# esp32-esp32s3_adapter.net
KiCad netlist of a schematic drawn in EAGLE
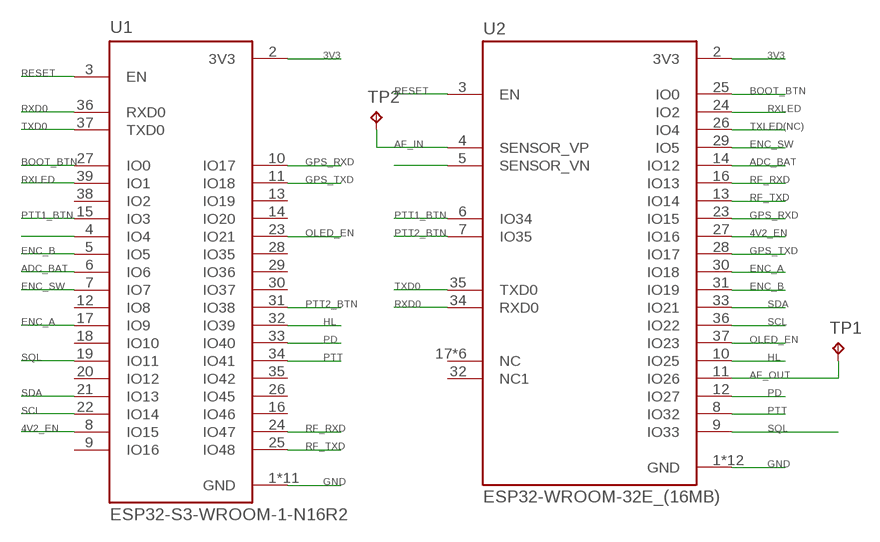
[diagram p0: schematic, sheet 1]

(export (version "E")
  (design (tool "Eeschema 10.0.6"))
  (components
    (comp (ref "TP1")
      (value "TPB1,27")
      (footprint "eagle-import:B1,27")
      (libsource (lib "eagle-import") (part "TPB1,27"))
    )
    (comp (ref "TP2")
      (value "TPB1,27")
      (footprint "eagle-import:B1,27")
      (libsource (lib "eagle-import") (part "TPB1,27"))
    )
    (comp (ref "U1")
      (value "ESP32-S3-WROOM-1-N16R2")
      (footprint "eagle-import:XCVR_ESP32-S3-WROOM-1-N16R2")
      (fields (field (name "MF") "Espressif Systems"))
      (libsource (lib "eagle-import") (part "ESP32-S3-WROOM-1-N16R2"))
    )
    (comp (ref "U2")
      (value "ESP32-WROOM-32E_(16MB)")
      (footprint "eagle-import:XCVR_ESP32-WROOM-32E_(16MB)")
      (fields (field (name "MF") "Espressif Systems") (field (name "MP") "ESP32-WROOM-32E (16MB)"))
      (libsource (lib "eagle-import") (part "ESP32-WROOM-32E_(16MB)"))
    )
  )
  (nets
    (net (code "1") (name "/3V3") (class "Default")
      (node (ref "U1") (pin "2") (pinfunction "3V3_2") (pintype "power_in"))
      (node (ref "U2") (pin "2") (pinfunction "3V3_2") (pintype "power_in"))
    )
    (net (code "2") (name "/4V2_EN") (class "Default")
      (node (ref "U1") (pin "8") (pinfunction "IO15_8") (pintype "bidirectional"))
      (node (ref "U2") (pin "27") (pinfunction "IO16_27") (pintype "bidirectional"))
    )
    (net (code "3") (name "/ADC_BAT") (class "Default")
      (node (ref "U1") (pin "6") (pinfunction "IO6_6") (pintype "bidirectional"))
      (node (ref "U2") (pin "14") (pinfunction "IO12_14") (pintype "bidirectional"))
    )
    (net (code "4") (name "/AF_IN") (class "Default")
      (node (ref "TP2") (pin "TP") (pinfunction "TP_TP") (pintype "input"))
      (node (ref "U2") (pin "4") (pinfunction "SENSOR_VP_4") (pintype "input"))
    )
    (net (code "5") (name "/AF_OUT") (class "Default")
      (node (ref "TP1") (pin "TP") (pinfunction "TP_TP") (pintype "input"))
      (node (ref "U2") (pin "11") (pinfunction "IO26_11") (pintype "bidirectional"))
    )
    (net (code "6") (name "/BOOT_BTN") (class "Default")
      (node (ref "U1") (pin "27") (pinfunction "IO0_27") (pintype "bidirectional"))
      (node (ref "U2") (pin "25") (pinfunction "IO0_25") (pintype "bidirectional"))
    )
    (net (code "7") (name "/ENC_A") (class "Default")
      (node (ref "U1") (pin "17") (pinfunction "IO9_17") (pintype "bidirectional"))
      (node (ref "U2") (pin "30") (pinfunction "IO18_30") (pintype "bidirectional"))
    )
    (net (code "8") (name "/ENC_B") (class "Default")
      (node (ref "U1") (pin "5") (pinfunction "IO5_5") (pintype "bidirectional"))
      (node (ref "U2") (pin "31") (pinfunction "IO19_31") (pintype "bidirectional"))
    )
    (net (code "9") (name "/ENC_SW") (class "Default")
      (node (ref "U1") (pin "7") (pinfunction "IO7_7") (pintype "bidirectional"))
      (node (ref "U2") (pin "29") (pinfunction "IO5_29") (pintype "bidirectional"))
    )
    (net (code "10") (name "/GND") (class "Default")
      (node (ref "U1") (pin "1") (pinfunction "GND_1") (pintype "power_in"))
      (node (ref "U1") (pin "40") (pinfunction "GND_40") (pintype "power_in"))
      (node (ref "U1") (pin "41_1") (pinfunction "GND_41_1") (pintype "power_in"))
      (node (ref "U1") (pin "41_2") (pinfunction "GND_41_2") (pintype "power_in"))
      (node (ref "U1") (pin "41_3") (pinfunction "GND_41_3") (pintype "power_in"))
      (node (ref "U1") (pin "41_4") (pinfunction "GND_41_4") (pintype "power_in"))
      (node (ref "U1") (pin "41_5") (pinfunction "GND_41_5") (pintype "power_in"))
      (node (ref "U1") (pin "41_6") (pinfunction "GND_41_6") (pintype "power_in"))
      (node (ref "U1") (pin "41_7") (pinfunction "GND_41_7") (pintype "power_in"))
      (node (ref "U1") (pin "41_8") (pinfunction "GND_41_8") (pintype "power_in"))
      (node (ref "U1") (pin "41_9") (pinfunction "GND_41_9") (pintype "power_in"))
      (node (ref "U2") (pin "1") (pinfunction "GND_1") (pintype "power_in"))
      (node (ref "U2") (pin "15") (pinfunction "GND_15") (pintype "power_in"))
      (node (ref "U2") (pin "38") (pinfunction "GND_38") (pintype "power_in"))
      (node (ref "U2") (pin "39_1") (pinfunction "GND_39_1") (pintype "power_in"))
      (node (ref "U2") (pin "39_2") (pinfunction "GND_39_2") (pintype "power_in"))
      (node (ref "U2") (pin "39_3") (pinfunction "GND_39_3") (pintype "power_in"))
      (node (ref "U2") (pin "39_4") (pinfunction "GND_39_4") (pintype "power_in"))
      (node (ref "U2") (pin "39_5") (pinfunction "GND_39_5") (pintype "power_in"))
      (node (ref "U2") (pin "39_6") (pinfunction "GND_39_6") (pintype "power_in"))
      (node (ref "U2") (pin "39_7") (pinfunction "GND_39_7") (pintype "power_in"))
      (node (ref "U2") (pin "39_8") (pinfunction "GND_39_8") (pintype "power_in"))
      (node (ref "U2") (pin "39_9") (pinfunction "GND_39_9") (pintype "power_in"))
    )
    (net (code "11") (name "/GPS_RXD") (class "Default")
      (node (ref "U1") (pin "10") (pinfunction "IO17_10") (pintype "bidirectional"))
      (node (ref "U2") (pin "23") (pinfunction "IO15_23") (pintype "bidirectional"))
    )
    (net (code "12") (name "/GPS_TXD") (class "Default")
      (node (ref "U1") (pin "11") (pinfunction "IO18_11") (pintype "bidirectional"))
      (node (ref "U2") (pin "28") (pinfunction "IO17_28") (pintype "bidirectional"))
    )
    (net (code "13") (name "/HL") (class "Default")
      (node (ref "U1") (pin "32") (pinfunction "IO39_32") (pintype "bidirectional"))
      (node (ref "U2") (pin "10") (pinfunction "IO25_10") (pintype "bidirectional"))
    )
    (net (code "14") (name "/OLED_EN") (class "Default")
      (node (ref "U1") (pin "23") (pinfunction "IO21_23") (pintype "bidirectional"))
      (node (ref "U2") (pin "37") (pinfunction "IO23_37") (pintype "bidirectional"))
    )
    (net (code "15") (name "/PD") (class "Default")
      (node (ref "U1") (pin "33") (pinfunction "IO40_33") (pintype "bidirectional"))
      (node (ref "U2") (pin "12") (pinfunction "IO27_12") (pintype "bidirectional"))
    )
    (net (code "16") (name "/PTT") (class "Default")
      (node (ref "U1") (pin "34") (pinfunction "IO41_34") (pintype "bidirectional"))
      (node (ref "U2") (pin "8") (pinfunction "IO32_8") (pintype "bidirectional"))
    )
    (net (code "17") (name "/PTT1_BTN") (class "Default")
      (node (ref "U1") (pin "15") (pinfunction "IO3_15") (pintype "bidirectional"))
      (node (ref "U2") (pin "6") (pinfunction "IO34_6") (pintype "input"))
    )
    (net (code "18") (name "/PTT2_BTN") (class "Default")
      (node (ref "U1") (pin "31") (pinfunction "IO38_31") (pintype "bidirectional"))
      (node (ref "U2") (pin "7") (pinfunction "IO35_7") (pintype "input"))
    )
    (net (code "19") (name "/RESET") (class "Default")
      (node (ref "U1") (pin "3") (pinfunction "EN_3") (pintype "input"))
      (node (ref "U2") (pin "3") (pinfunction "EN_3") (pintype "input"))
    )
    (net (code "20") (name "/RF_RXD") (class "Default")
      (node (ref "U1") (pin "24") (pinfunction "IO47_24") (pintype "bidirectional"))
      (node (ref "U2") (pin "16") (pinfunction "IO13_16") (pintype "bidirectional"))
    )
    (net (code "21") (name "/RF_TXD") (class "Default")
      (node (ref "U1") (pin "25") (pinfunction "IO48_25") (pintype "bidirectional"))
      (node (ref "U2") (pin "13") (pinfunction "IO14_13") (pintype "bidirectional"))
    )
    (net (code "22") (name "/RXD0") (class "Default")
      (node (ref "U1") (pin "36") (pinfunction "RXD0_36") (pintype "bidirectional"))
      (node (ref "U2") (pin "34") (pinfunction "RXD0_34") (pintype "bidirectional"))
    )
    (net (code "23") (name "/RXLED") (class "Default")
      (node (ref "U1") (pin "39") (pinfunction "IO1_39") (pintype "bidirectional"))
      (node (ref "U2") (pin "24") (pinfunction "IO2_24") (pintype "bidirectional"))
    )
    (net (code "24") (name "/SCL") (class "Default")
      (node (ref "U1") (pin "22") (pinfunction "IO14_22") (pintype "bidirectional"))
      (node (ref "U2") (pin "36") (pinfunction "IO22_36") (pintype "bidirectional"))
    )
    (net (code "25") (name "/SDA") (class "Default")
      (node (ref "U1") (pin "21") (pinfunction "IO13_21") (pintype "bidirectional"))
      (node (ref "U2") (pin "33") (pinfunction "IO21_33") (pintype "bidirectional"))
    )
    (net (code "26") (name "/SQL") (class "Default")
      (node (ref "U1") (pin "19") (pinfunction "IO11_19") (pintype "bidirectional"))
      (node (ref "U2") (pin "9") (pinfunction "IO33_9") (pintype "bidirectional"))
    )
    (net (code "27") (name "/TXD0") (class "Default")
      (node (ref "U1") (pin "37") (pinfunction "TXD0_37") (pintype "bidirectional"))
      (node (ref "U2") (pin "35") (pinfunction "TXD0_35") (pintype "bidirectional"))
    )
    (net (code "28") (name "/TXLED(NC)") (class "Default")
      (node (ref "U2") (pin "26") (pinfunction "IO4_26") (pintype "bidirectional"))
    )
    (net (code "29") (name "unconnected-(U1-IO2-Pad38)") (class "Default")
      (node (ref "U1") (pin "38") (pinfunction "IO2_38") (pintype "bidirectional"))
    )
    (net (code "30") (name "unconnected-(U1-IO4-Pad4)") (class "Default")
      (node (ref "U1") (pin "4") (pinfunction "IO4_4") (pintype "bidirectional"))
    )
    (net (code "31") (name "unconnected-(U1-IO8-Pad12)") (class "Default")
      (node (ref "U1") (pin "12") (pinfunction "IO8_12") (pintype "bidirectional"))
    )
    (net (code "32") (name "unconnected-(U1-IO10-Pad18)") (class "Default")
      (node (ref "U1") (pin "18") (pinfunction "IO10_18") (pintype "bidirectional"))
    )
    (net (code "33") (name "unconnected-(U1-IO12-Pad20)") (class "Default")
      (node (ref "U1") (pin "20") (pinfunction "IO12_20") (pintype "bidirectional"))
    )
    (net (code "34") (name "unconnected-(U1-IO16-Pad9)") (class "Default")
      (node (ref "U1") (pin "9") (pinfunction "IO16_9") (pintype "bidirectional"))
    )
    (net (code "35") (name "unconnected-(U1-IO19-Pad13)") (class "Default")
      (node (ref "U1") (pin "13") (pinfunction "IO19_13") (pintype "bidirectional"))
    )
    (net (code "36") (name "unconnected-(U1-IO20-Pad14)") (class "Default")
      (node (ref "U1") (pin "14") (pinfunction "IO20_14") (pintype "bidirectional"))
    )
    (net (code "37") (name "unconnected-(U1-IO35-Pad28)") (class "Default")
      (node (ref "U1") (pin "28") (pinfunction "IO35_28") (pintype "bidirectional"))
    )
    (net (code "38") (name "unconnected-(U1-IO36-Pad29)") (class "Default")
      (node (ref "U1") (pin "29") (pinfunction "IO36_29") (pintype "bidirectional"))
    )
    (net (code "39") (name "unconnected-(U1-IO37-Pad30)") (class "Default")
      (node (ref "U1") (pin "30") (pinfunction "IO37_30") (pintype "bidirectional"))
    )
    (net (code "40") (name "unconnected-(U1-IO42-Pad35)") (class "Default")
      (node (ref "U1") (pin "35") (pinfunction "IO42_35") (pintype "bidirectional"))
    )
    (net (code "41") (name "unconnected-(U1-IO45-Pad26)") (class "Default")
      (node (ref "U1") (pin "26") (pinfunction "IO45_26") (pintype "bidirectional"))
    )
    (net (code "42") (name "unconnected-(U1-IO46-Pad16)") (class "Default")
      (node (ref "U1") (pin "16") (pinfunction "IO46_16") (pintype "bidirectional"))
    )
    (net (code "43") (name "unconnected-(U2-NC-Pad17)") (class "Default")
      (node (ref "U2") (pin "17") (pinfunction "NC_17") (pintype "no_connect"))
    )
    (net (code "44") (name "unconnected-(U2-NC-Pad18)") (class "Default")
      (node (ref "U2") (pin "18") (pinfunction "NC_18") (pintype "no_connect"))
    )
    (net (code "45") (name "unconnected-(U2-NC-Pad19)") (class "Default")
      (node (ref "U2") (pin "19") (pinfunction "NC_19") (pintype "no_connect"))
    )
    (net (code "46") (name "unconnected-(U2-NC-Pad20)") (class "Default")
      (node (ref "U2") (pin "20") (pinfunction "NC_20") (pintype "no_connect"))
    )
    (net (code "47") (name "unconnected-(U2-NC-Pad21)") (class "Default")
      (node (ref "U2") (pin "21") (pinfunction "NC_21") (pintype "no_connect"))
    )
    (net (code "48") (name "unconnected-(U2-NC-Pad22)") (class "Default")
      (node (ref "U2") (pin "22") (pinfunction "NC_22") (pintype "no_connect"))
    )
    (net (code "49") (name "unconnected-(U2-NC1-Pad32)") (class "Default")
      (node (ref "U2") (pin "32") (pinfunction "NC1_32") (pintype "no_connect"))
    )
    (net (code "50") (name "unconnected-(U2-SENSOR_VN-Pad5)") (class "Default")
      (node (ref "U2") (pin "5") (pinfunction "SENSOR_VN_5") (pintype "input"))
    )
  )
)
